# Un_Net_v1_1.net
KiCad netlist of a schematic drawn in EAGLE
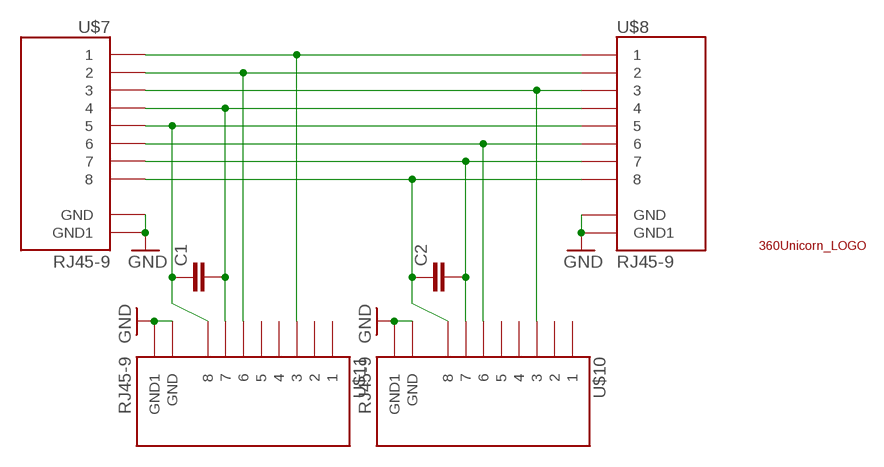
[diagram p0: schematic, sheet 1]

(export (version "E")
  (design (tool "Eeschema 10.0.6"))
  (components
    (comp (ref "C1")
      (value "CAP1206")
      (footprint "eagle-import:1206")
      (libsource (lib "eagle-import") (part "CAP1206"))
    )
    (comp (ref "C2")
      (value "CAP1206")
      (footprint "eagle-import:1206")
      (libsource (lib "eagle-import") (part "CAP1206"))
    )
    (comp (ref "U$1")
      (value "360UNICORN_LOGO_1Z")
      (footprint "eagle-import:360UNICORN_LOGO_1Z")
      (libsource (lib "eagle-import") (part "360UNICORN_LOGO_1Z"))
    )
    (comp (ref "U$7")
      (value "RJ45-9")
      (footprint "eagle-import:RJ45-9")
      (libsource (lib "eagle-import") (part "RJ45-9"))
    )
    (comp (ref "U$8")
      (value "RJ45-9")
      (footprint "eagle-import:RJ45-9")
      (libsource (lib "eagle-import") (part "RJ45-9"))
    )
    (comp (ref "U$10")
      (value "RJ45-9")
      (footprint "eagle-import:RJ45-9")
      (libsource (lib "eagle-import") (part "RJ45-9"))
    )
    (comp (ref "U$11")
      (value "RJ45-9")
      (footprint "eagle-import:RJ45-9")
      (libsource (lib "eagle-import") (part "RJ45-9"))
    )
  )
  (nets
    (net (code "1") (name "GND") (class "Default")
      (node (ref "U$10") (pin "10") (pinfunction "GND1_10") (pintype "bidirectional"))
      (node (ref "U$10") (pin "9") (pinfunction "GND_9") (pintype "bidirectional"))
      (node (ref "U$11") (pin "10") (pinfunction "GND1_10") (pintype "bidirectional"))
      (node (ref "U$11") (pin "9") (pinfunction "GND_9") (pintype "bidirectional"))
      (node (ref "U$7") (pin "10") (pinfunction "GND1_10") (pintype "bidirectional"))
      (node (ref "U$7") (pin "9") (pinfunction "GND_9") (pintype "bidirectional"))
      (node (ref "U$8") (pin "10") (pinfunction "GND1_10") (pintype "bidirectional"))
      (node (ref "U$8") (pin "9") (pinfunction "GND_9") (pintype "bidirectional"))
    )
    (net (code "2") (name "Net-(C1-Pad1)") (class "Default")
      (node (ref "C1") (pin "1") (pinfunction "1_1") (pintype "passive"))
      (node (ref "U$11") (pin "8") (pinfunction "8_8") (pintype "bidirectional"))
      (node (ref "U$7") (pin "5") (pinfunction "5_5") (pintype "bidirectional"))
      (node (ref "U$8") (pin "5") (pinfunction "5_5") (pintype "bidirectional"))
    )
    (net (code "3") (name "Net-(C1-Pad2)") (class "Default")
      (node (ref "C1") (pin "2") (pinfunction "2_2") (pintype "passive"))
      (node (ref "U$11") (pin "7") (pinfunction "7_7") (pintype "bidirectional"))
      (node (ref "U$7") (pin "4") (pinfunction "4_4") (pintype "bidirectional"))
      (node (ref "U$8") (pin "4") (pinfunction "4_4") (pintype "bidirectional"))
    )
    (net (code "4") (name "Net-(C2-Pad1)") (class "Default")
      (node (ref "C2") (pin "1") (pinfunction "1_1") (pintype "passive"))
      (node (ref "U$10") (pin "8") (pinfunction "8_8") (pintype "bidirectional"))
      (node (ref "U$7") (pin "8") (pinfunction "8_8") (pintype "bidirectional"))
      (node (ref "U$8") (pin "8") (pinfunction "8_8") (pintype "bidirectional"))
    )
    (net (code "5") (name "Net-(C2-Pad2)") (class "Default")
      (node (ref "C2") (pin "2") (pinfunction "2_2") (pintype "passive"))
      (node (ref "U$10") (pin "7") (pinfunction "7_7") (pintype "bidirectional"))
      (node (ref "U$7") (pin "7") (pinfunction "7_7") (pintype "bidirectional"))
      (node (ref "U$8") (pin "7") (pinfunction "7_7") (pintype "bidirectional"))
    )
    (net (code "6") (name "Net-(U$10-Pad3)") (class "Default")
      (node (ref "U$10") (pin "3") (pinfunction "3_3") (pintype "bidirectional"))
      (node (ref "U$7") (pin "3") (pinfunction "3_3") (pintype "bidirectional"))
      (node (ref "U$8") (pin "3") (pinfunction "3_3") (pintype "bidirectional"))
    )
    (net (code "7") (name "Net-(U$10-Pad6)") (class "Default")
      (node (ref "U$10") (pin "6") (pinfunction "6_6") (pintype "bidirectional"))
      (node (ref "U$7") (pin "6") (pinfunction "6_6") (pintype "bidirectional"))
      (node (ref "U$8") (pin "6") (pinfunction "6_6") (pintype "bidirectional"))
    )
    (net (code "8") (name "Net-(U$11-Pad3)") (class "Default")
      (node (ref "U$11") (pin "3") (pinfunction "3_3") (pintype "bidirectional"))
      (node (ref "U$7") (pin "1") (pinfunction "1_1") (pintype "bidirectional"))
      (node (ref "U$8") (pin "1") (pinfunction "1_1") (pintype "bidirectional"))
    )
    (net (code "9") (name "Net-(U$11-Pad6)") (class "Default")
      (node (ref "U$11") (pin "6") (pinfunction "6_6") (pintype "bidirectional"))
      (node (ref "U$7") (pin "2") (pinfunction "2_2") (pintype "bidirectional"))
      (node (ref "U$8") (pin "2") (pinfunction "2_2") (pintype "bidirectional"))
    )
    (net (code "10") (name "unconnected-(U$10-Pad1)") (class "Default")
      (node (ref "U$10") (pin "1") (pinfunction "1_1") (pintype "bidirectional"))
    )
    (net (code "11") (name "unconnected-(U$10-Pad2)") (class "Default")
      (node (ref "U$10") (pin "2") (pinfunction "2_2") (pintype "bidirectional"))
    )
    (net (code "12") (name "unconnected-(U$10-Pad4)") (class "Default")
      (node (ref "U$10") (pin "4") (pinfunction "4_4") (pintype "bidirectional"))
    )
    (net (code "13") (name "unconnected-(U$10-Pad5)") (class "Default")
      (node (ref "U$10") (pin "5") (pinfunction "5_5") (pintype "bidirectional"))
    )
    (net (code "14") (name "unconnected-(U$11-Pad1)") (class "Default")
      (node (ref "U$11") (pin "1") (pinfunction "1_1") (pintype "bidirectional"))
    )
    (net (code "15") (name "unconnected-(U$11-Pad2)") (class "Default")
      (node (ref "U$11") (pin "2") (pinfunction "2_2") (pintype "bidirectional"))
    )
    (net (code "16") (name "unconnected-(U$11-Pad4)") (class "Default")
      (node (ref "U$11") (pin "4") (pinfunction "4_4") (pintype "bidirectional"))
    )
    (net (code "17") (name "unconnected-(U$11-Pad5)") (class "Default")
      (node (ref "U$11") (pin "5") (pinfunction "5_5") (pintype "bidirectional"))
    )
  )
)
